# Sheet_1.net
KiCad netlist of a schematic drawn in EasyEDA
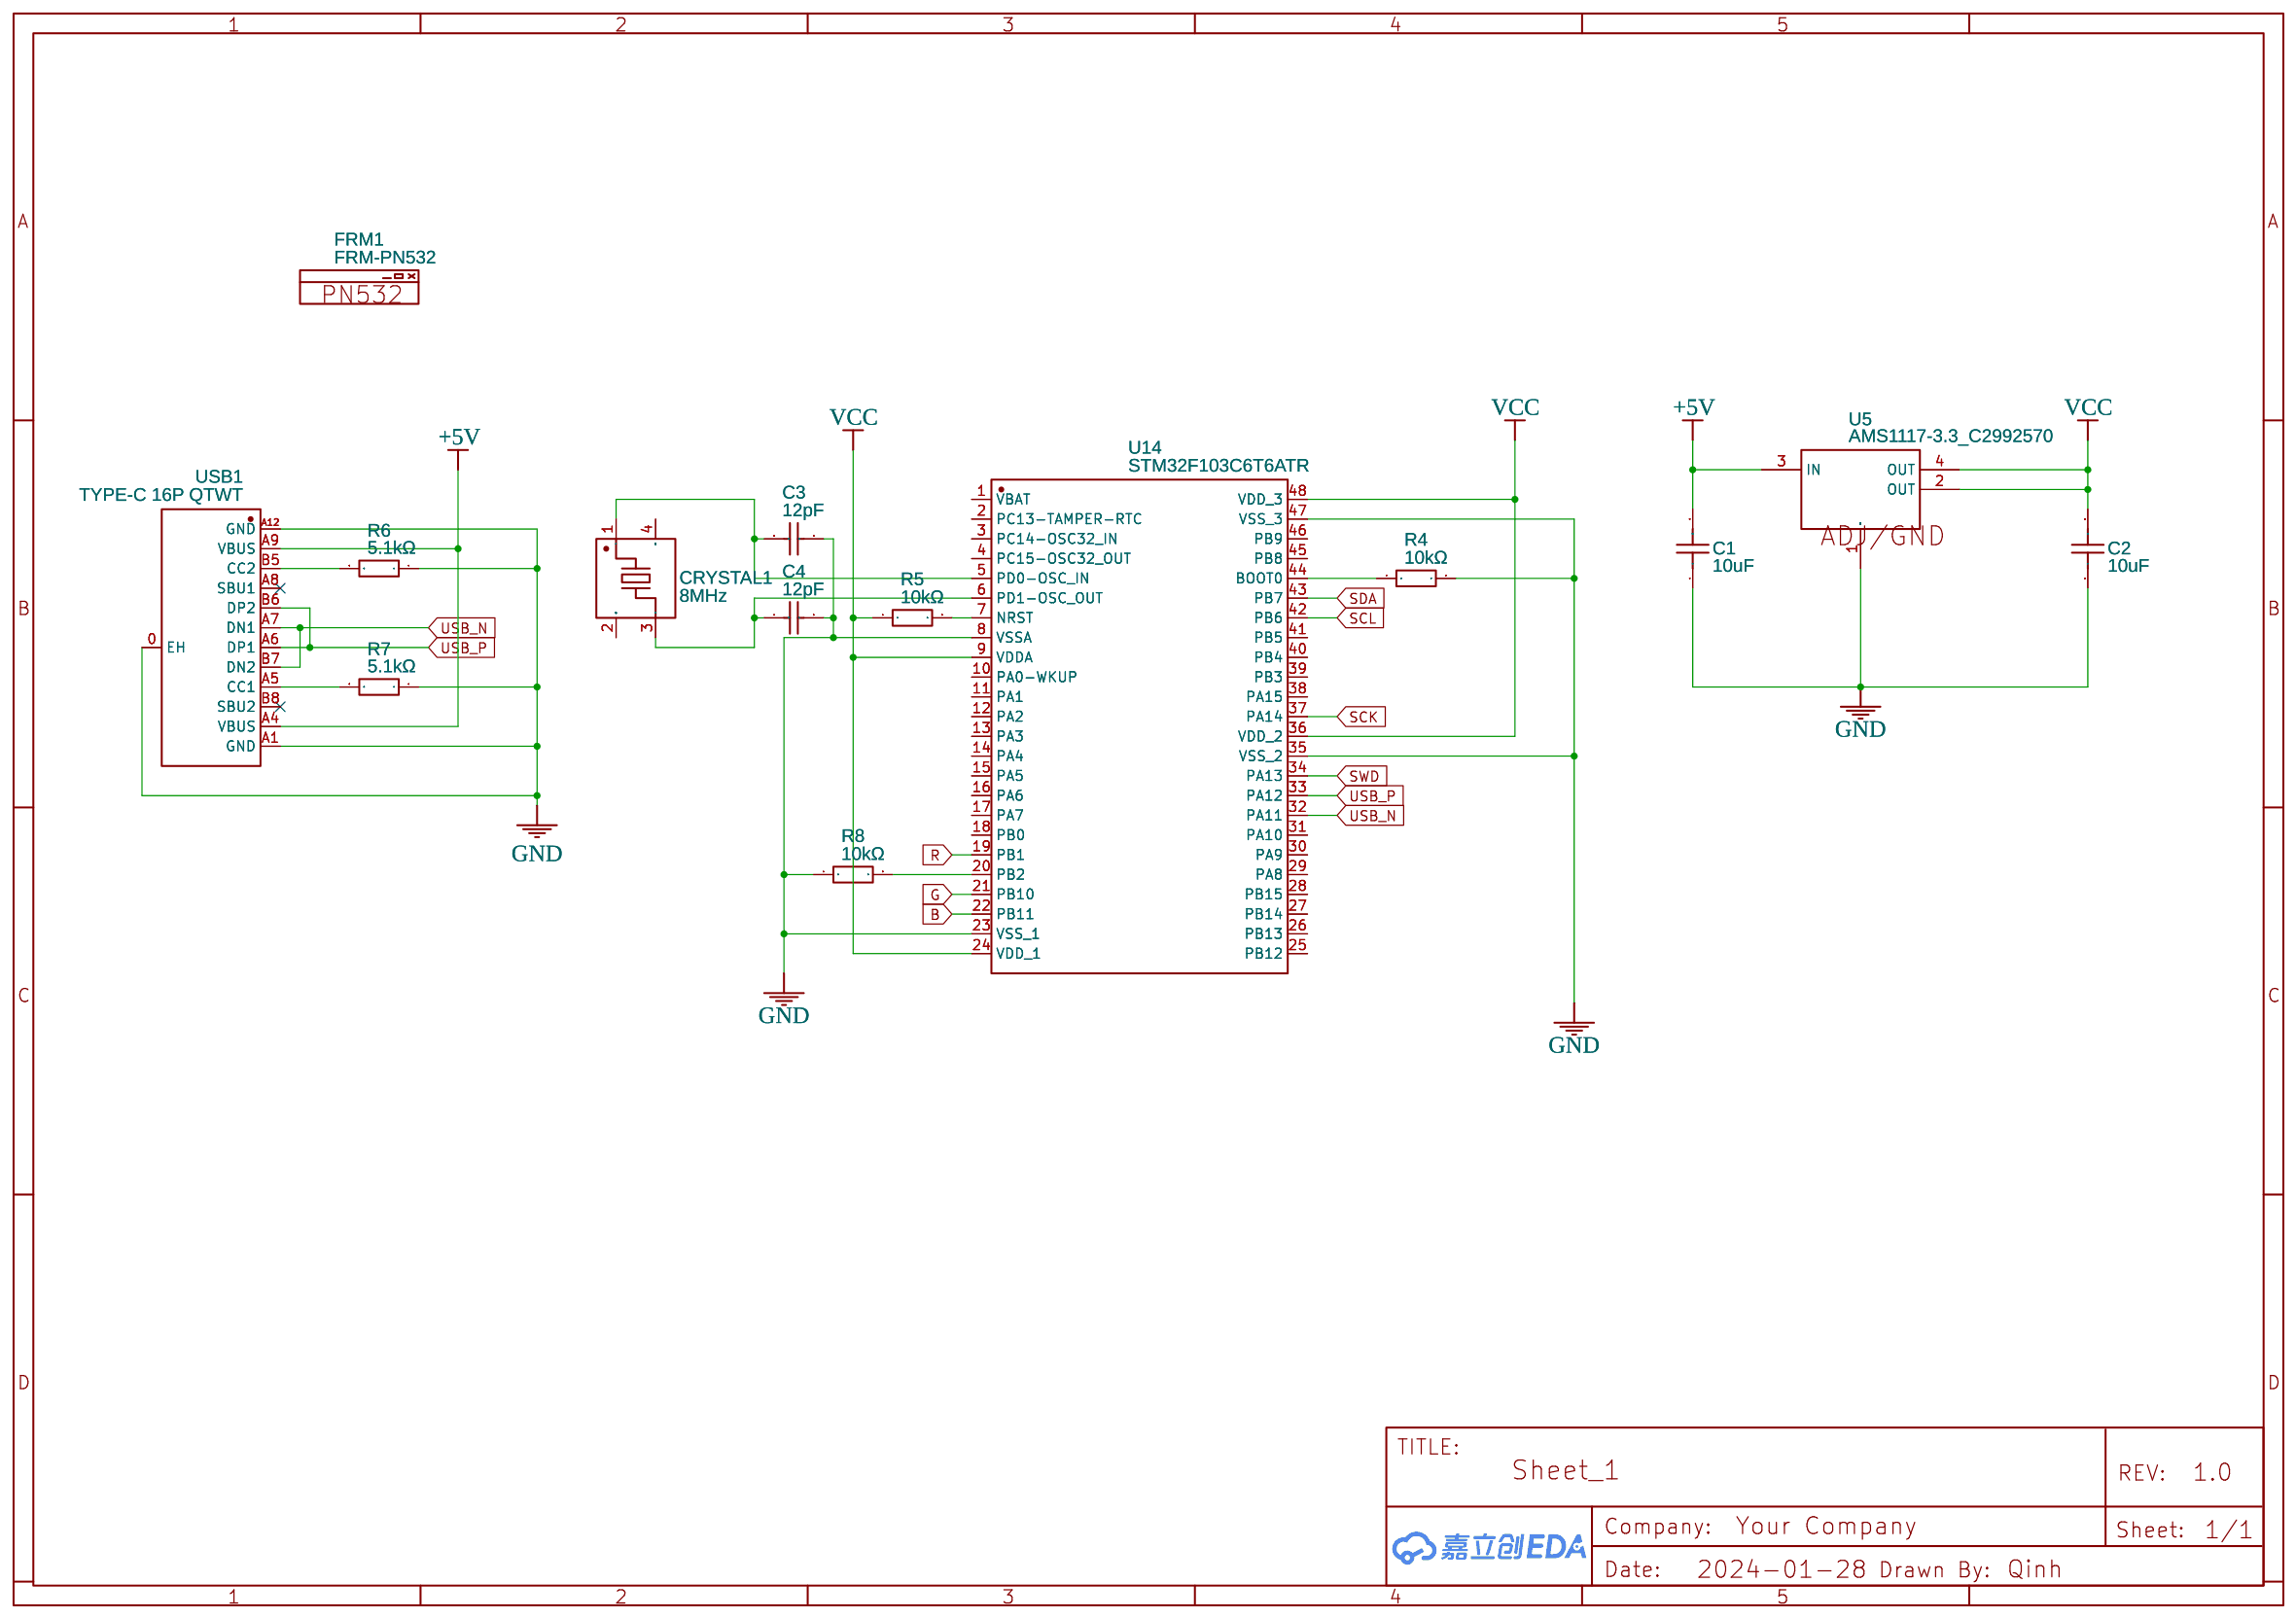
[diagram p0: schematic sheet]

(export (version "E")
  (design (tool "Eeschema 10.0.6"))
  (components
    (comp (ref "C1")
      (value "10uF")
      (fields
        (field (name "Manufacturer Part") "CL10A106KP8NNNC")
        (field (name "Manufacturer") "SAMSUNG(三星)")
      )
      (libsource (lib "") (part "CL10A106KP8NNNC"))
    )
    (comp (ref "C2")
      (value "10uF")
      (fields
        (field (name "Manufacturer Part") "CL10A106KP8NNNC")
        (field (name "Manufacturer") "SAMSUNG(三星)")
      )
      (libsource (lib "") (part "CL10A106KP8NNNC"))
    )
    (comp (ref "C3")
      (value "12pF")
      (fields
        (field (name "Manufacturer Part") "CL10C120JB8NNNC")
        (field (name "Manufacturer") "SAMSUNG(三星)")
      )
      (libsource (lib "") (part "CL10C120JB8NNNC"))
    )
    (comp (ref "C4")
      (value "12pF")
      (fields
        (field (name "Manufacturer Part") "CL10C120JB8NNNC")
        (field (name "Manufacturer") "SAMSUNG(三星)")
      )
      (libsource (lib "") (part "CL10C120JB8NNNC"))
    )
    (comp (ref "CRYSTAL1")
      (value "8MHz")
      (fields (field (name "Manufacturer Part") "CF4008M00012001") (field (name "Manufacturer") "HUAXIN(华昕)"))
      (libsource (lib "") (part "CF4008M00012001"))
    )
    (comp (ref "FRM1") (value "FRM-PN532") (libsource (lib "") (part "FRM-PN532")))
    (comp (ref "R4")
      (value "10kΩ")
      (fields
        (field (name "Manufacturer Part") "0603WAF1002T5E")
        (field (name "Manufacturer") "UNI-ROYAL(厚声)")
      )
      (libsource (lib "") (part "0603WAF1002T5E"))
    )
    (comp (ref "R5")
      (value "10kΩ")
      (fields
        (field (name "Manufacturer Part") "0603WAF1002T5E")
        (field (name "Manufacturer") "UNI-ROYAL(厚声)")
      )
      (libsource (lib "") (part "0603WAF1002T5E"))
    )
    (comp (ref "R6")
      (value "5.1kΩ")
      (fields
        (field (name "BOM_Manufacturer Part") "RMC06035.1K1%N")
        (field (name "BOM_Supplier Part") "C269716")
      )
      (libsource (lib "") (part "RMC06035.1K1%N"))
    )
    (comp (ref "R7")
      (value "5.1kΩ")
      (fields
        (field (name "BOM_Manufacturer Part") "RMC06035.1K1%N")
        (field (name "BOM_Supplier Part") "C269716")
      )
      (libsource (lib "") (part "RMC06035.1K1%N"))
    )
    (comp (ref "R8")
      (value "10kΩ")
      (fields
        (field (name "Manufacturer Part") "0603WAF1002T5E")
        (field (name "Manufacturer") "UNI-ROYAL(厚声)")
      )
      (libsource (lib "") (part "0603WAF1002T5E"))
    )
    (comp (ref "U5")
      (value "AMS1117-3.3_C2992570")
      (fields
        (field (name "BOM_Manufacturer Part") "AMS1117-3.3")
        (field (name "BOM_Supplier Part") "C2992570")
      )
      (libsource (lib "") (part "AMS1117-3.3_C2992570"))
    )
    (comp (ref "U14")
      (value "STM32F103C6T6ATR")
      (fields (field (name "Manufacturer") "ST(意法半导体)"))
      (libsource (lib "") (part "STM32F103C6T6ATR"))
    )
    (comp (ref "USB1")
      (value "TYPE-C 16P QTWT")
      (fields (field (name "Manufacturer") "SHOU HAN(首韩)"))
      (libsource (lib "") (part "TYPE-C 16P QTWT"))
    )
  )
  (nets
    (net (code "1") (name "+5V") (class "Default")
      (node (ref "C1") (pin "2") (pinfunction "2_2") (pintype "unspecified"))
      (node (ref "U5") (pin "3") (pinfunction "IN_3") (pintype "passive"))
      (node (ref "USB1") (pin "A4") (pinfunction "VBUS_A4") (pintype "unspecified"))
      (node (ref "USB1") (pin "A9") (pinfunction "VBUS_A9") (pintype "unspecified"))
    )
    (net (code "2") (name "B") (class "Default")
      (node (ref "U14") (pin "22") (pinfunction "PB11_22") (pintype "unspecified"))
    )
    (net (code "3") (name "G") (class "Default")
      (node (ref "U14") (pin "21") (pinfunction "PB10_21") (pintype "unspecified"))
    )
    (net (code "4") (name "GND") (class "Default")
      (node (ref "C1") (pin "1") (pinfunction "1_1") (pintype "unspecified"))
      (node (ref "C2") (pin "1") (pinfunction "1_1") (pintype "unspecified"))
      (node (ref "C3") (pin "2") (pinfunction "2_2") (pintype "input"))
      (node (ref "C4") (pin "2") (pinfunction "2_2") (pintype "input"))
      (node (ref "R4") (pin "2") (pinfunction "2_2") (pintype "input"))
      (node (ref "R6") (pin "1") (pinfunction "1_1") (pintype "unspecified"))
      (node (ref "R7") (pin "1") (pinfunction "1_1") (pintype "unspecified"))
      (node (ref "R8") (pin "1") (pinfunction "1_1") (pintype "input"))
      (node (ref "U14") (pin "23") (pinfunction "VSS_1_23") (pintype "unspecified"))
      (node (ref "U14") (pin "35") (pinfunction "VSS_2_35") (pintype "unspecified"))
      (node (ref "U14") (pin "47") (pinfunction "VSS_3_47") (pintype "unspecified"))
      (node (ref "U14") (pin "8") (pinfunction "VSSA_8") (pintype "unspecified"))
      (node (ref "U5") (pin "1") (pinfunction "ADJ/GND_1") (pintype "passive"))
      (node (ref "USB1") (pin "0") (pinfunction "EH_0") (pintype "unspecified"))
      (node (ref "USB1") (pin "A1") (pinfunction "GND_A1") (pintype "unspecified"))
      (node (ref "USB1") (pin "A12") (pinfunction "GND_A12") (pintype "unspecified"))
    )
    (net (code "5") (name "Net-(U14-BOOT0)") (class "Default")
      (node (ref "R4") (pin "1") (pinfunction "1_1") (pintype "input"))
      (node (ref "U14") (pin "44") (pinfunction "BOOT0_44") (pintype "unspecified"))
    )
    (net (code "6") (name "Net-(U14-NRST)") (class "Default")
      (node (ref "R5") (pin "2") (pinfunction "2_2") (pintype "input"))
      (node (ref "U14") (pin "7") (pinfunction "NRST_7") (pintype "unspecified"))
    )
    (net (code "7") (name "Net-(U14-PB2)") (class "Default")
      (node (ref "R8") (pin "2") (pinfunction "2_2") (pintype "input"))
      (node (ref "U14") (pin "20") (pinfunction "PB2_20") (pintype "unspecified"))
    )
    (net (code "8") (name "Net-(U14-PD0-OSC_IN)") (class "Default")
      (node (ref "C3") (pin "1") (pinfunction "1_1") (pintype "input"))
      (node (ref "CRYSTAL1") (pin "1") (pinfunction "1_1") (pintype "input"))
      (node (ref "U14") (pin "5") (pinfunction "PD0-OSC_IN_5") (pintype "unspecified"))
    )
    (net (code "9") (name "Net-(U14-PD1-OSC_OUT)") (class "Default")
      (node (ref "C4") (pin "1") (pinfunction "1_1") (pintype "input"))
      (node (ref "CRYSTAL1") (pin "3") (pinfunction "3_3") (pintype "input"))
      (node (ref "U14") (pin "6") (pinfunction "PD1-OSC_OUT_6") (pintype "unspecified"))
    )
    (net (code "10") (name "Net-(USB1-CC1)") (class "Default")
      (node (ref "R7") (pin "2") (pinfunction "2_2") (pintype "unspecified"))
      (node (ref "USB1") (pin "A5") (pinfunction "CC1_A5") (pintype "unspecified"))
    )
    (net (code "11") (name "Net-(USB1-CC2)") (class "Default")
      (node (ref "R6") (pin "2") (pinfunction "2_2") (pintype "unspecified"))
      (node (ref "USB1") (pin "B5") (pinfunction "CC2_B5") (pintype "unspecified"))
    )
    (net (code "12") (name "R") (class "Default")
      (node (ref "U14") (pin "19") (pinfunction "PB1_19") (pintype "unspecified"))
    )
    (net (code "13") (name "SCK") (class "Default")
      (node (ref "U14") (pin "37") (pinfunction "PA14_37") (pintype "unspecified"))
    )
    (net (code "14") (name "SCL") (class "Default")
      (node (ref "U14") (pin "42") (pinfunction "PB6_42") (pintype "unspecified"))
    )
    (net (code "15") (name "SDA") (class "Default")
      (node (ref "U14") (pin "43") (pinfunction "PB7_43") (pintype "unspecified"))
    )
    (net (code "16") (name "SWD") (class "Default")
      (node (ref "U14") (pin "34") (pinfunction "PA13_34") (pintype "unspecified"))
    )
    (net (code "17") (name "USB_N") (class "Default")
      (node (ref "U14") (pin "32") (pinfunction "PA11_32") (pintype "unspecified"))
      (node (ref "USB1") (pin "A7") (pinfunction "DN1_A7") (pintype "unspecified"))
      (node (ref "USB1") (pin "B7") (pinfunction "DN2_B7") (pintype "unspecified"))
    )
    (net (code "18") (name "USB_P") (class "Default")
      (node (ref "U14") (pin "33") (pinfunction "PA12_33") (pintype "unspecified"))
      (node (ref "USB1") (pin "A6") (pinfunction "DP1_A6") (pintype "unspecified"))
      (node (ref "USB1") (pin "B6") (pinfunction "DP2_B6") (pintype "unspecified"))
    )
    (net (code "19") (name "VCC") (class "Default")
      (node (ref "C2") (pin "2") (pinfunction "2_2") (pintype "unspecified"))
      (node (ref "R5") (pin "1") (pinfunction "1_1") (pintype "input"))
      (node (ref "U14") (pin "24") (pinfunction "VDD_1_24") (pintype "unspecified"))
      (node (ref "U14") (pin "36") (pinfunction "VDD_2_36") (pintype "unspecified"))
      (node (ref "U14") (pin "48") (pinfunction "VDD_3_48") (pintype "unspecified"))
      (node (ref "U14") (pin "9") (pinfunction "VDDA_9") (pintype "unspecified"))
      (node (ref "U5") (pin "2") (pinfunction "OUT_2") (pintype "passive"))
      (node (ref "U5") (pin "4") (pinfunction "OUT_4") (pintype "passive"))
    )
    (net (code "20") (name "unconnected-(CRYSTAL1-GND-Pad2)") (class "Default")
      (node (ref "CRYSTAL1") (pin "2") (pinfunction "GND_2") (pintype "input"))
    )
    (net (code "21") (name "unconnected-(CRYSTAL1-GND-Pad4)") (class "Default")
      (node (ref "CRYSTAL1") (pin "4") (pinfunction "GND_4") (pintype "input"))
    )
    (net (code "22") (name "unconnected-(U14-PA0-WKUP-Pad10)") (class "Default")
      (node (ref "U14") (pin "10") (pinfunction "PA0-WKUP_10") (pintype "unspecified"))
    )
    (net (code "23") (name "unconnected-(U14-PA1-Pad11)") (class "Default")
      (node (ref "U14") (pin "11") (pinfunction "PA1_11") (pintype "unspecified"))
    )
    (net (code "24") (name "unconnected-(U14-PA2-Pad12)") (class "Default")
      (node (ref "U14") (pin "12") (pinfunction "PA2_12") (pintype "unspecified"))
    )
    (net (code "25") (name "unconnected-(U14-PA3-Pad13)") (class "Default")
      (node (ref "U14") (pin "13") (pinfunction "PA3_13") (pintype "unspecified"))
    )
    (net (code "26") (name "unconnected-(U14-PA4-Pad14)") (class "Default")
      (node (ref "U14") (pin "14") (pinfunction "PA4_14") (pintype "unspecified"))
    )
    (net (code "27") (name "unconnected-(U14-PA5-Pad15)") (class "Default")
      (node (ref "U14") (pin "15") (pinfunction "PA5_15") (pintype "unspecified"))
    )
    (net (code "28") (name "unconnected-(U14-PA6-Pad16)") (class "Default")
      (node (ref "U14") (pin "16") (pinfunction "PA6_16") (pintype "unspecified"))
    )
    (net (code "29") (name "unconnected-(U14-PA7-Pad17)") (class "Default")
      (node (ref "U14") (pin "17") (pinfunction "PA7_17") (pintype "unspecified"))
    )
    (net (code "30") (name "unconnected-(U14-PA8-Pad29)") (class "Default")
      (node (ref "U14") (pin "29") (pinfunction "PA8_29") (pintype "unspecified"))
    )
    (net (code "31") (name "unconnected-(U14-PA9-Pad30)") (class "Default")
      (node (ref "U14") (pin "30") (pinfunction "PA9_30") (pintype "unspecified"))
    )
    (net (code "32") (name "unconnected-(U14-PA10-Pad31)") (class "Default")
      (node (ref "U14") (pin "31") (pinfunction "PA10_31") (pintype "unspecified"))
    )
    (net (code "33") (name "unconnected-(U14-PA15-Pad38)") (class "Default")
      (node (ref "U14") (pin "38") (pinfunction "PA15_38") (pintype "unspecified"))
    )
    (net (code "34") (name "unconnected-(U14-PB0-Pad18)") (class "Default")
      (node (ref "U14") (pin "18") (pinfunction "PB0_18") (pintype "unspecified"))
    )
    (net (code "35") (name "unconnected-(U14-PB3-Pad39)") (class "Default")
      (node (ref "U14") (pin "39") (pinfunction "PB3_39") (pintype "unspecified"))
    )
    (net (code "36") (name "unconnected-(U14-PB4-Pad40)") (class "Default")
      (node (ref "U14") (pin "40") (pinfunction "PB4_40") (pintype "unspecified"))
    )
    (net (code "37") (name "unconnected-(U14-PB5-Pad41)") (class "Default")
      (node (ref "U14") (pin "41") (pinfunction "PB5_41") (pintype "unspecified"))
    )
    (net (code "38") (name "unconnected-(U14-PB8-Pad45)") (class "Default")
      (node (ref "U14") (pin "45") (pinfunction "PB8_45") (pintype "unspecified"))
    )
    (net (code "39") (name "unconnected-(U14-PB9-Pad46)") (class "Default")
      (node (ref "U14") (pin "46") (pinfunction "PB9_46") (pintype "unspecified"))
    )
    (net (code "40") (name "unconnected-(U14-PB12-Pad25)") (class "Default")
      (node (ref "U14") (pin "25") (pinfunction "PB12_25") (pintype "unspecified"))
    )
    (net (code "41") (name "unconnected-(U14-PB13-Pad26)") (class "Default")
      (node (ref "U14") (pin "26") (pinfunction "PB13_26") (pintype "unspecified"))
    )
    (net (code "42") (name "unconnected-(U14-PB14-Pad27)") (class "Default")
      (node (ref "U14") (pin "27") (pinfunction "PB14_27") (pintype "unspecified"))
    )
    (net (code "43") (name "unconnected-(U14-PB15-Pad28)") (class "Default")
      (node (ref "U14") (pin "28") (pinfunction "PB15_28") (pintype "unspecified"))
    )
    (net (code "44") (name "unconnected-(U14-PC13-TAMPER-RTC-Pad2)") (class "Default")
      (node (ref "U14") (pin "2") (pinfunction "PC13-TAMPER-RTC_2") (pintype "unspecified"))
    )
    (net (code "45") (name "unconnected-(U14-PC14-OSC32_IN-Pad3)") (class "Default")
      (node (ref "U14") (pin "3") (pinfunction "PC14-OSC32_IN_3") (pintype "unspecified"))
    )
    (net (code "46") (name "unconnected-(U14-PC15-OSC32_OUT-Pad4)") (class "Default")
      (node (ref "U14") (pin "4") (pinfunction "PC15-OSC32_OUT_4") (pintype "unspecified"))
    )
    (net (code "47") (name "unconnected-(U14-VBAT-Pad1)") (class "Default")
      (node (ref "U14") (pin "1") (pinfunction "VBAT_1") (pintype "unspecified"))
    )
    (net (code "48") (name "unconnected-(USB1-SBU1-PadA8)") (class "Default")
      (node (ref "USB1") (pin "A8") (pinfunction "SBU1_A8") (pintype "unspecified+no_connect"))
    )
    (net (code "49") (name "unconnected-(USB1-SBU2-PadB8)") (class "Default")
      (node (ref "USB1") (pin "B8") (pinfunction "SBU2_B8") (pintype "unspecified+no_connect"))
    )
  )
)
